# NDMK.net
KiCad netlist of a schematic drawn in Altium Designer
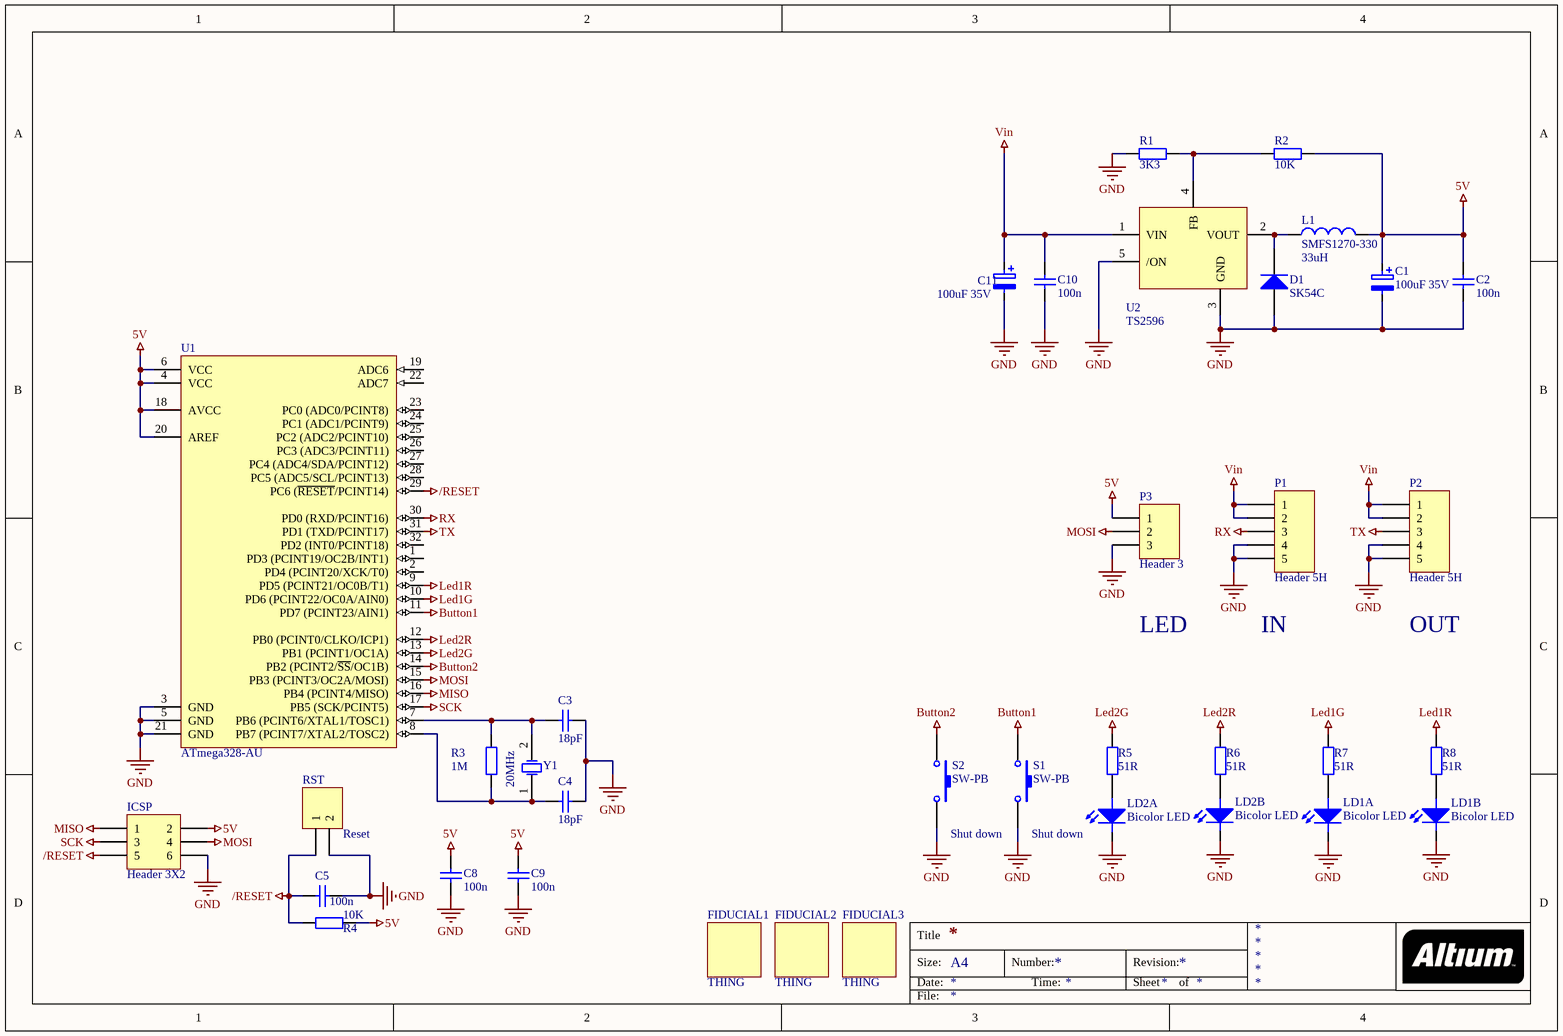
[diagram p0: NDMK.SchDoc]

(export (version "E")
  (design (tool "Eeschema 10.0.6"))
  (components
    (comp (ref "C1")
      (value "100uF 35V")
      (footprint "CAPSMD0605")
      (description "Polarised Capacitator")
      (libsource (lib "supranet") (part "CapPol _1"))
    )
    (comp (ref "C2")
      (value "100n")
      (footprint "supranet_new:C1206")
      (description "Capacitor")
      (fields (field (name "PUBLISHER") "Altium Limited"))
      (libsource (lib "RFID Citac - RS232") (part "Cap"))
    )
    (comp (ref "C3")
      (value "18pF")
      (footprint "C1206")
      (description "Capacitor (Semiconductor SIM Model)")
      (fields (field (name "PUBLISHER") "Altium Limited"))
      (libsource (lib "Miscellaneous Devices") (part "Cap Semi"))
    )
    (comp (ref "C4")
      (value "18pF")
      (footprint "C1206")
      (description "Capacitor (Semiconductor SIM Model)")
      (fields (field (name "PUBLISHER") "Altium Limited"))
      (libsource (lib "Miscellaneous Devices") (part "Cap Semi"))
    )
    (comp (ref "C5")
      (value "100n")
      (footprint "supranet_new:C1206")
      (description "Capacitor")
      (fields (field (name "PUBLISHER") "Altium Limited"))
      (libsource (lib "RFID Citac - RS232") (part "Cap"))
    )
    (comp (ref "C8")
      (value "100n")
      (footprint "supranet_new:C1206")
      (description "Capacitor")
      (fields (field (name "PUBLISHER") "Altium Limited"))
      (libsource (lib "RFID Citac - RS232") (part "Cap"))
    )
    (comp (ref "C9")
      (value "100n")
      (footprint "supranet_new:C1206")
      (description "Capacitor")
      (fields (field (name "PUBLISHER") "Altium Limited"))
      (libsource (lib "RFID Citac - RS232") (part "Cap"))
    )
    (comp (ref "C10")
      (value "100n")
      (footprint "supranet_new:C1206")
      (description "Capacitor")
      (fields (field (name "PUBLISHER") "Altium Limited"))
      (libsource (lib "RFID Citac - RS232") (part "Cap"))
    )
    (comp (ref "C11")
      (value "100uF 35V")
      (footprint "SMD 1010")
      (description "Polarised Capacitator")
      (libsource (lib "supranet") (part "CapPol _1"))
    )
    (comp (ref "D1")
      (value "SK54C")
      (footprint "D-SMC")
      (description "Default Diode")
      (fields (field (name "PUBLISHER") "Altium Limited"))
      (libsource (lib "Miscellaneous Devices") (part "Diode"))
    )
    (comp (ref "FIDUCIAL1")
      (value "THING")
      (footprint "FIDUCIAL")
      (description "Something")
      (libsource (lib "supranet") (part "THING"))
    )
    (comp (ref "FIDUCIAL2")
      (value "THING")
      (footprint "FIDUCIAL")
      (description "Something")
      (libsource (lib "supranet") (part "THING"))
    )
    (comp (ref "FIDUCIAL3")
      (value "THING")
      (footprint "FIDUCIAL")
      (description "Something")
      (libsource (lib "supranet") (part "THING"))
    )
    (comp (ref "ICSP")
      (value "Header 3X2")
      (footprint "supranet_new:HDR2X3")
      (description "Header, 3-Pin, Dual row")
      (fields (field (name "PUBLISHER") "Altium Limited"))
      (libsource (lib "Miscellaneous Connectors") (part "Header 3X2"))
    )
    (comp (ref "L1")
      (value "SMFS1270-330")
      (footprint "smd1212")
      (description "Inductor")
      (fields (field (name "ALTIUM_VALUE") "33uH") (field (name "PUBLISHER") "Altium Limited"))
      (libsource (lib "Miscellaneous Devices") (part "Inductor"))
    )
    (comp (ref "LD1")
      (value "Bicolor LED")
      (footprint "11-22SURSYGC")
      (description "11-22SURSYGC/S530-A2/TR8")
      (libsource (lib "supranet") (part "Bicolor LED"))
    )
    (comp (ref "LD2")
      (value "Bicolor LED")
      (footprint "11-22SURSYGC")
      (description "11-22SURSYGC/S530-A2/TR8")
      (libsource (lib "supranet") (part "Bicolor LED"))
    )
    (comp (ref "P1")
      (value "Header 5H")
      (footprint "HDR1X5H")
      (description "Header, 5-Pin, Right Angle")
      (fields (field (name "PUBLISHER") "Altium Limited"))
      (libsource (lib "Miscellaneous Connectors") (part "Header 5H"))
    )
    (comp (ref "P2")
      (value "Header 5H")
      (footprint "HDR1X5H")
      (description "Header, 5-Pin, Right Angle")
      (fields (field (name "PUBLISHER") "Altium Limited"))
      (libsource (lib "Miscellaneous Connectors") (part "Header 5H"))
    )
    (comp (ref "P3")
      (value "Header 3")
      (footprint "HDR1X3")
      (description "Header, 3-Pin")
      (fields (field (name "PUBLISHER") "Altium Limited"))
      (libsource (lib "Miscellaneous Connectors") (part "Header 3"))
    )
    (comp (ref "R1")
      (value "3K3")
      (footprint "R1206")
      (description "Resistor")
      (fields (field (name "PUBLISHER") "Altium Limited"))
      (libsource (lib "Miscellaneous Devices") (part "Res2"))
    )
    (comp (ref "R2")
      (value "10K")
      (footprint "R1206")
      (description "Resistor")
      (fields (field (name "PUBLISHER") "Altium Limited"))
      (libsource (lib "Miscellaneous Devices") (part "Res2"))
    )
    (comp (ref "R3")
      (value "1M")
      (footprint "R1206")
      (description "Resistor")
      (fields (field (name "PUBLISHER") "Altium Limited"))
      (libsource (lib "") (part "Res2_2"))
    )
    (comp (ref "R4")
      (value "10K")
      (footprint "R1206")
      (description "Resistor")
      (fields (field (name "PUBLISHER") "Altium Limited"))
      (libsource (lib "") (part "Res2_2"))
    )
    (comp (ref "R5")
      (value "51R")
      (footprint "R1206")
      (description "Resistor")
      (fields (field (name "PUBLISHER") "Altium Limited"))
      (libsource (lib "") (part "Res2_1"))
    )
    (comp (ref "R6")
      (value "51R")
      (footprint "R1206")
      (description "Resistor")
      (fields (field (name "PUBLISHER") "Altium Limited"))
      (libsource (lib "") (part "Res2_1"))
    )
    (comp (ref "R7")
      (value "51R")
      (footprint "R1206")
      (description "Resistor")
      (fields (field (name "PUBLISHER") "Altium Limited"))
      (libsource (lib "") (part "Res2_1"))
    )
    (comp (ref "R8")
      (value "51R")
      (footprint "R1206")
      (description "Resistor")
      (fields (field (name "PUBLISHER") "Altium Limited"))
      (libsource (lib "") (part "Res2_1"))
    )
    (comp (ref "RST")
      (value "Reset")
      (footprint "HDR1X2")
      (description "DO NOT POPULATE")
      (fields (field (name "PUBLISHER") "Altium Limited"))
      (libsource (lib "Miscellaneous Connectors") (part "Header 2"))
    )
    (comp (ref "S1")
      (value "SW-PB")
      (footprint "MULTICOMP - MC32850 - SWITCH")
      (description "Switch")
      (fields (field (name "PUBLISHER") "Altium Limited"))
      (libsource (lib "Miscellaneous Devices") (part "SW-PB"))
    )
    (comp (ref "S2")
      (value "SW-PB")
      (footprint "MULTICOMP - MC32850 - SWITCH")
      (description "Switch")
      (fields (field (name "PUBLISHER") "Altium Limited"))
      (libsource (lib "Miscellaneous Devices") (part "SW-PB"))
    )
    (comp (ref "U1")
      (value "ATmega328-AU")
      (footprint "32A_N")
      (fields (field (name "PUBLISHER") "Altium Limited"))
      (libsource (lib "Atmel Microcontroller 8-Bit megaAVR") (part "ATmega328-AU"))
    )
    (comp (ref "U2")
      (value "TS2596")
      (footprint "TO-263-5L")
      (description "3A / 150KHz Buck DC-DC Converter")
      (libsource (lib "supranet") (part "TS2596"))
    )
    (comp (ref "Y1")
      (value "20MHz")
      (footprint "xtal")
      (description "Crystal Oscillator")
      (fields (field (name "PUBLISHER") "Altium Limited"))
      (libsource (lib "Miscellaneous Devices") (part "XTAL"))
    )
  )
  (nets
    (net (code "1") (name "5V") (class "Default")
      (node (ref "C1") (pin "1") (pinfunction "1_1") (pintype "passive"))
      (node (ref "C2") (pin "2") (pinfunction "2_2") (pintype "passive"))
      (node (ref "C8") (pin "2") (pinfunction "2_2") (pintype "passive"))
      (node (ref "C9") (pin "2") (pinfunction "2_2") (pintype "passive"))
      (node (ref "ICSP") (pin "2") (pinfunction "2_2") (pintype "passive"))
      (node (ref "L1") (pin "2") (pinfunction "2_2") (pintype "passive"))
      (node (ref "P3") (pin "1") (pinfunction "1_1") (pintype "passive"))
      (node (ref "R2") (pin "1") (pinfunction "1_1") (pintype "passive"))
      (node (ref "R4") (pin "2") (pinfunction "2_2") (pintype "passive"))
      (node (ref "U1") (pin "18") (pinfunction "AVCC_18") (pintype "power_in"))
      (node (ref "U1") (pin "20") (pinfunction "AREF_20") (pintype "passive"))
      (node (ref "U1") (pin "4") (pinfunction "VCC_4") (pintype "power_in"))
      (node (ref "U1") (pin "6") (pinfunction "VCC_6") (pintype "power_in"))
    )
    (net (code "2") (name "Button1") (class "Default")
      (node (ref "S1") (pin "1") (pinfunction "1_1") (pintype "passive"))
      (node (ref "U1") (pin "11") (pinfunction "PD7_(PCINT23/AIN1)_11") (pintype "bidirectional"))
    )
    (net (code "3") (name "Button2") (class "Default")
      (node (ref "S2") (pin "1") (pinfunction "1_1") (pintype "passive"))
      (node (ref "U1") (pin "14") (pinfunction "PB2_(PCINT2/~{SS}/OC1B)_14") (pintype "bidirectional"))
    )
    (net (code "4") (name "GND") (class "Default")
      (node (ref "C1") (pin "2") (pinfunction "2_2") (pintype "passive"))
      (node (ref "C10") (pin "1") (pinfunction "1_1") (pintype "passive"))
      (node (ref "C11") (pin "2") (pinfunction "2_2") (pintype "passive"))
      (node (ref "C2") (pin "1") (pinfunction "1_1") (pintype "passive"))
      (node (ref "C3") (pin "2") (pinfunction "2_2") (pintype "passive"))
      (node (ref "C4") (pin "2") (pinfunction "2_2") (pintype "passive"))
      (node (ref "C5") (pin "1") (pinfunction "1_1") (pintype "passive"))
      (node (ref "C8") (pin "1") (pinfunction "1_1") (pintype "passive"))
      (node (ref "C9") (pin "1") (pinfunction "1_1") (pintype "passive"))
      (node (ref "D1") (pin "1") (pinfunction "A_1") (pintype "passive"))
      (node (ref "ICSP") (pin "6") (pinfunction "6_6") (pintype "passive"))
      (node (ref "LD1") (pin "1") (pintype "passive"))
      (node (ref "LD1") (pin "3") (pintype "passive"))
      (node (ref "LD2") (pin "1") (pintype "passive"))
      (node (ref "LD2") (pin "3") (pintype "passive"))
      (node (ref "P1") (pin "4") (pinfunction "4_4") (pintype "passive"))
      (node (ref "P1") (pin "5") (pinfunction "5_5") (pintype "passive"))
      (node (ref "P2") (pin "4") (pinfunction "4_4") (pintype "passive"))
      (node (ref "P2") (pin "5") (pinfunction "5_5") (pintype "passive"))
      (node (ref "P3") (pin "3") (pinfunction "3_3") (pintype "passive"))
      (node (ref "R1") (pin "2") (pinfunction "2_2") (pintype "passive"))
      (node (ref "RST") (pin "2") (pinfunction "2_2") (pintype "passive"))
      (node (ref "S1") (pin "2") (pinfunction "2_2") (pintype "passive"))
      (node (ref "S2") (pin "2") (pinfunction "2_2") (pintype "passive"))
      (node (ref "U1") (pin "21") (pinfunction "GND_21") (pintype "power_in"))
      (node (ref "U1") (pin "3") (pinfunction "GND_3") (pintype "power_in"))
      (node (ref "U1") (pin "5") (pinfunction "GND_5") (pintype "power_in"))
      (node (ref "U2") (pin "3") (pinfunction "GND_3") (pintype "passive"))
      (node (ref "U2") (pin "5") (pinfunction "/ON_5") (pintype "passive"))
    )
    (net (code "5") (name "Led1G") (class "Default")
      (node (ref "R7") (pin "2") (pinfunction "2_2") (pintype "passive"))
      (node (ref "U1") (pin "10") (pinfunction "PD6_(PCINT22/OC0A/AIN0)_10") (pintype "bidirectional"))
    )
    (net (code "6") (name "Led1R") (class "Default")
      (node (ref "R8") (pin "2") (pinfunction "2_2") (pintype "passive"))
      (node (ref "U1") (pin "9") (pinfunction "PD5_(PCINT21/OC0B/T1)_9") (pintype "bidirectional"))
    )
    (net (code "7") (name "Led2G") (class "Default")
      (node (ref "R5") (pin "2") (pinfunction "2_2") (pintype "passive"))
      (node (ref "U1") (pin "13") (pinfunction "PB1_(PCINT1/OC1A)_13") (pintype "bidirectional"))
    )
    (net (code "8") (name "Led2R") (class "Default")
      (node (ref "R6") (pin "2") (pinfunction "2_2") (pintype "passive"))
      (node (ref "U1") (pin "12") (pinfunction "PB0_(PCINT0/CLKO/ICP1)_12") (pintype "bidirectional"))
    )
    (net (code "9") (name "MISO") (class "Default")
      (node (ref "ICSP") (pin "1") (pinfunction "1_1") (pintype "passive"))
      (node (ref "U1") (pin "16") (pinfunction "PB4_(PCINT4/MISO)_16") (pintype "bidirectional"))
    )
    (net (code "10") (name "MOSI") (class "Default")
      (node (ref "ICSP") (pin "4") (pinfunction "4_4") (pintype "passive"))
      (node (ref "P3") (pin "2") (pinfunction "2_2") (pintype "passive"))
      (node (ref "U1") (pin "15") (pinfunction "PB3_(PCINT3/OC2A/MOSI)_15") (pintype "bidirectional"))
    )
    (net (code "11") (name "Net-(D1-K)") (class "Default")
      (node (ref "D1") (pin "2") (pinfunction "K_2") (pintype "passive"))
      (node (ref "L1") (pin "1") (pinfunction "1_1") (pintype "passive"))
      (node (ref "U2") (pin "2") (pinfunction "VOUT_2") (pintype "passive"))
    )
    (net (code "12") (name "Net-(LD1-Pad2)") (class "Default")
      (node (ref "LD1") (pin "2") (pintype "passive"))
      (node (ref "R8") (pin "1") (pinfunction "1_1") (pintype "passive"))
    )
    (net (code "13") (name "Net-(LD1-Pad4)") (class "Default")
      (node (ref "LD1") (pin "4") (pintype "passive"))
      (node (ref "R7") (pin "1") (pinfunction "1_1") (pintype "passive"))
    )
    (net (code "14") (name "Net-(LD2-Pad2)") (class "Default")
      (node (ref "LD2") (pin "2") (pintype "passive"))
      (node (ref "R6") (pin "1") (pinfunction "1_1") (pintype "passive"))
    )
    (net (code "15") (name "Net-(LD2-Pad4)") (class "Default")
      (node (ref "LD2") (pin "4") (pintype "passive"))
      (node (ref "R5") (pin "1") (pinfunction "1_1") (pintype "passive"))
    )
    (net (code "16") (name "Net-(U1-PB6_(PCINT6{slash}XTAL1{slash}TOSC1))") (class "Default")
      (node (ref "C3") (pin "1") (pinfunction "1_1") (pintype "passive"))
      (node (ref "R3") (pin "2") (pinfunction "2_2") (pintype "passive"))
      (node (ref "U1") (pin "7") (pinfunction "PB6_(PCINT6/XTAL1/TOSC1)_7") (pintype "bidirectional"))
      (node (ref "Y1") (pin "2") (pinfunction "OSC2_2") (pintype "passive"))
    )
    (net (code "17") (name "Net-(U1-PB7_(PCINT7{slash}XTAL2{slash}TOSC2))") (class "Default")
      (node (ref "C4") (pin "1") (pinfunction "1_1") (pintype "passive"))
      (node (ref "R3") (pin "1") (pinfunction "1_1") (pintype "passive"))
      (node (ref "U1") (pin "8") (pinfunction "PB7_(PCINT7/XTAL2/TOSC2)_8") (pintype "bidirectional"))
      (node (ref "Y1") (pin "1") (pinfunction "OSC1_1") (pintype "passive"))
    )
    (net (code "18") (name "Net-(U2-FB)") (class "Default")
      (node (ref "R1") (pin "1") (pinfunction "1_1") (pintype "passive"))
      (node (ref "R2") (pin "2") (pinfunction "2_2") (pintype "passive"))
      (node (ref "U2") (pin "4") (pinfunction "FB_4") (pintype "passive"))
    )
    (net (code "19") (name "RX") (class "Default")
      (node (ref "P1") (pin "3") (pinfunction "3_3") (pintype "passive"))
      (node (ref "U1") (pin "30") (pinfunction "PD0_(RXD/PCINT16)_30") (pintype "bidirectional"))
    )
    (net (code "20") (name "SCK") (class "Default")
      (node (ref "ICSP") (pin "3") (pinfunction "3_3") (pintype "passive"))
      (node (ref "U1") (pin "17") (pinfunction "PB5_(SCK/PCINT5)_17") (pintype "bidirectional"))
    )
    (net (code "21") (name "TX") (class "Default")
      (node (ref "P2") (pin "3") (pinfunction "3_3") (pintype "passive"))
      (node (ref "U1") (pin "31") (pinfunction "PD1_(TXD/PCINT17)_31") (pintype "bidirectional"))
    )
    (net (code "22") (name "Vin") (class "Default")
      (node (ref "C10") (pin "2") (pinfunction "2_2") (pintype "passive"))
      (node (ref "C11") (pin "1") (pinfunction "1_1") (pintype "passive"))
      (node (ref "P1") (pin "1") (pinfunction "1_1") (pintype "passive"))
      (node (ref "P1") (pin "2") (pinfunction "2_2") (pintype "passive"))
      (node (ref "P2") (pin "1") (pinfunction "1_1") (pintype "passive"))
      (node (ref "P2") (pin "2") (pinfunction "2_2") (pintype "passive"))
      (node (ref "U2") (pin "1") (pinfunction "VIN_1") (pintype "passive"))
    )
    (net (code "23") (name "unconnected-(U1-ADC6-Pad19)") (class "Default")
      (node (ref "U1") (pin "19") (pinfunction "ADC6_19") (pintype "input"))
    )
    (net (code "24") (name "unconnected-(U1-ADC7-Pad22)") (class "Default")
      (node (ref "U1") (pin "22") (pinfunction "ADC7_22") (pintype "input"))
    )
    (net (code "25") (name "unconnected-(U1-PC0_(ADC0{slash}PCINT8)-Pad23)") (class "Default")
      (node (ref "U1") (pin "23") (pinfunction "PC0_(ADC0/PCINT8)_23") (pintype "bidirectional"))
    )
    (net (code "26") (name "unconnected-(U1-PC1_(ADC1{slash}PCINT9)-Pad24)") (class "Default")
      (node (ref "U1") (pin "24") (pinfunction "PC1_(ADC1/PCINT9)_24") (pintype "bidirectional"))
    )
    (net (code "27") (name "unconnected-(U1-PC2_(ADC2{slash}PCINT10)-Pad25)") (class "Default")
      (node (ref "U1") (pin "25") (pinfunction "PC2_(ADC2/PCINT10)_25") (pintype "bidirectional"))
    )
    (net (code "28") (name "unconnected-(U1-PC3_(ADC3{slash}PCINT11)-Pad26)") (class "Default")
      (node (ref "U1") (pin "26") (pinfunction "PC3_(ADC3/PCINT11)_26") (pintype "bidirectional"))
    )
    (net (code "29") (name "unconnected-(U1-PC4_(ADC4{slash}SDA{slash}PCINT12)-Pad27)") (class "Default")
      (node (ref "U1") (pin "27") (pinfunction "PC4_(ADC4/SDA/PCINT12)_27") (pintype "bidirectional"))
    )
    (net (code "30") (name "unconnected-(U1-PC5_(ADC5{slash}SCL{slash}PCINT13)-Pad28)") (class "Default")
      (node (ref "U1") (pin "28") (pinfunction "PC5_(ADC5/SCL/PCINT13)_28") (pintype "bidirectional"))
    )
    (net (code "31") (name "unconnected-(U1-PD2_(INT0{slash}PCINT18)-Pad32)") (class "Default")
      (node (ref "U1") (pin "32") (pinfunction "PD2_(INT0/PCINT18)_32") (pintype "bidirectional"))
    )
    (net (code "32") (name "unconnected-(U1-PD3_(PCINT19{slash}OC2B{slash}INT1)-Pad1)") (class "Default")
      (node (ref "U1") (pin "1") (pinfunction "PD3_(PCINT19/OC2B/INT1)_1") (pintype "bidirectional"))
    )
    (net (code "33") (name "unconnected-(U1-PD4_(PCINT20{slash}XCK{slash}T0)-Pad2)") (class "Default")
      (node (ref "U1") (pin "2") (pinfunction "PD4_(PCINT20/XCK/T0)_2") (pintype "bidirectional"))
    )
    (net (code "34") (name "{slash}RESET") (class "Default")
      (node (ref "C5") (pin "2") (pinfunction "2_2") (pintype "passive"))
      (node (ref "ICSP") (pin "5") (pinfunction "5_5") (pintype "passive"))
      (node (ref "R4") (pin "1") (pinfunction "1_1") (pintype "passive"))
      (node (ref "RST") (pin "1") (pinfunction "1_1") (pintype "passive"))
      (node (ref "U1") (pin "29") (pinfunction "PC6_(~{RESET}/PCINT14)_29") (pintype "bidirectional"))
    )
  )
)
